# Main.net
KiCad netlist of a schematic drawn in Altium Designer
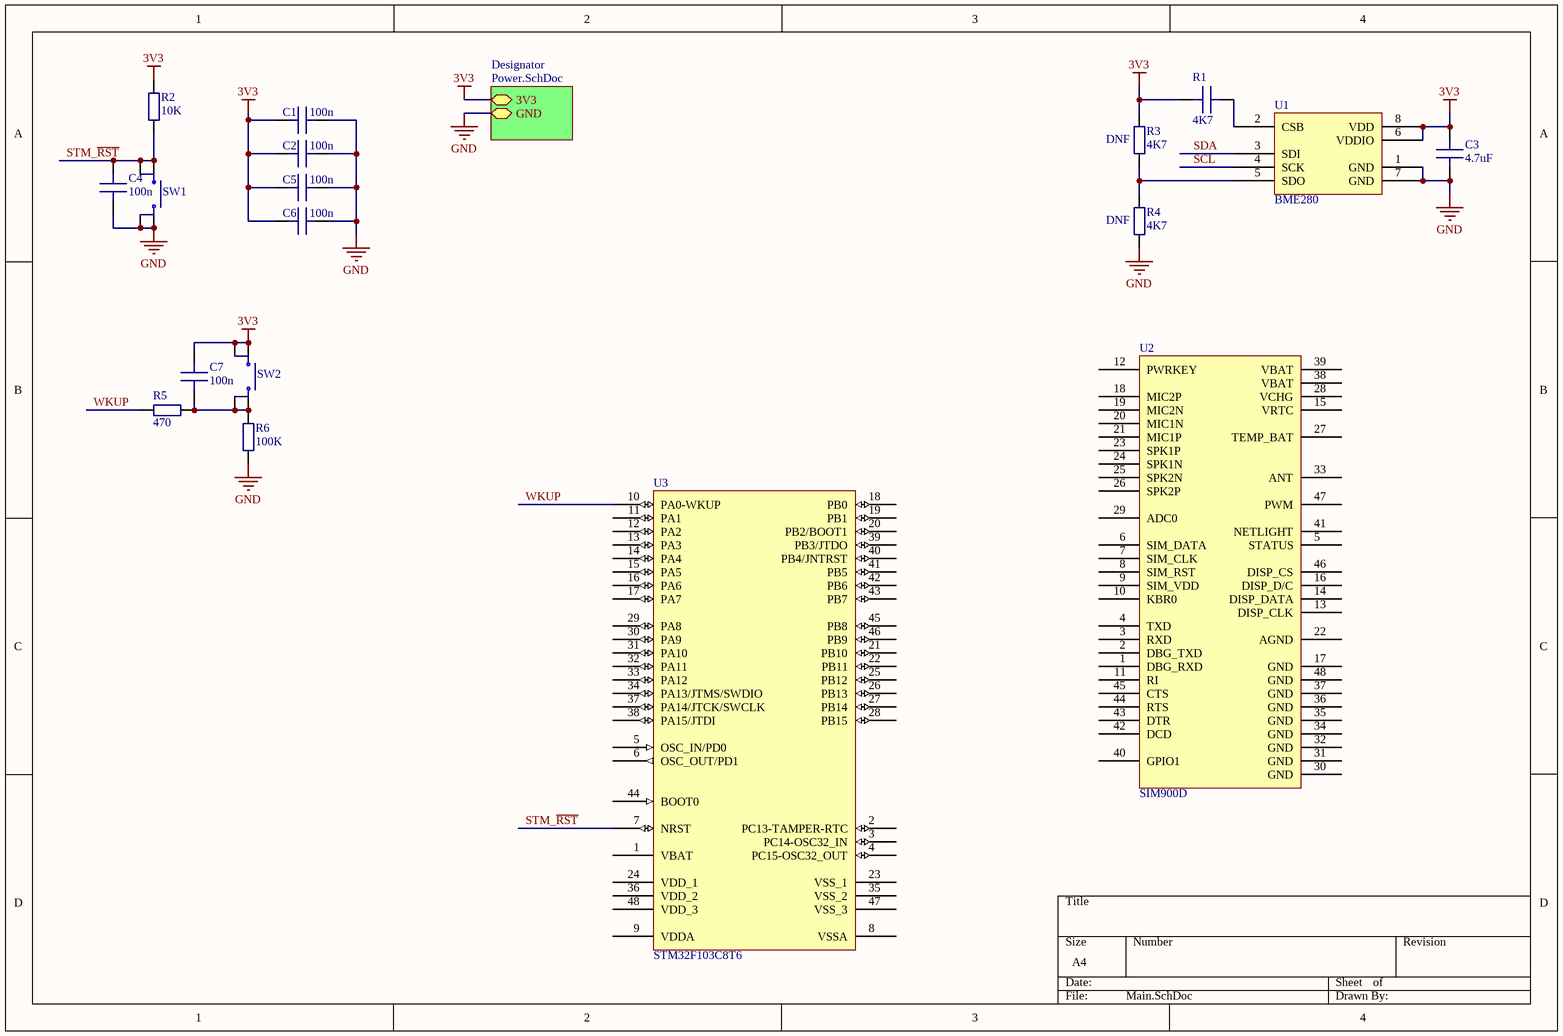
[diagram p0: Main.SchDoc]

(export (version "E")
  (design (tool "Eeschema 10.0.6"))
  (components
    (comp (ref "C1")
      (value "100n")
      (footprint "C0604")
      (description "Capacitor 0603 100n")
      (libsource (lib "ComponentsLib") (part "C0603_100n"))
    )
    (comp (ref "C2")
      (value "100n")
      (footprint "C0604")
      (description "Capacitor 0603 100n")
      (libsource (lib "ComponentsLib") (part "C0603_100n"))
    )
    (comp (ref "C3")
      (value "4.7uF")
      (footprint "C0805")
      (description "Capacitor 0805 4.7uF")
      (libsource (lib "ComponentsLib") (part "C0805_4u7"))
    )
    (comp (ref "C4")
      (value "100n")
      (footprint "C0604")
      (description "Capacitor 0603 100n")
      (libsource (lib "ComponentsLib") (part "C0603_100n"))
    )
    (comp (ref "C5")
      (value "100n")
      (footprint "C0604")
      (description "Capacitor 0603 100n")
      (libsource (lib "ComponentsLib") (part "C0603_100n"))
    )
    (comp (ref "C6")
      (value "100n")
      (footprint "C0604")
      (description "Capacitor 0603 100n")
      (libsource (lib "ComponentsLib") (part "C0603_100n"))
    )
    (comp (ref "C7")
      (value "100n")
      (footprint "C0604")
      (description "Capacitor 0603 100n")
      (libsource (lib "ComponentsLib") (part "C0603_100n"))
    )
    (comp (ref "R1")
      (value "4K7")
      (footprint "R0805")
      (description "Resistor 0805 4K7")
      (libsource (lib "ComponentsLib") (part "R0805_4k7"))
    )
    (comp (ref "R2")
      (value "10K")
      (footprint "R0805")
      (description "Resistor 0805 10K")
      (libsource (lib "ComponentsLib") (part "R0805_10K"))
    )
    (comp (ref "R3")
      (value "4K7")
      (footprint "R0805")
      (description "Resistor 0805 4K7")
      (libsource (lib "") (part "R0805_4k7_1"))
    )
    (comp (ref "R4")
      (value "4K7")
      (footprint "R0805")
      (description "Resistor 0805 4K7")
      (libsource (lib "") (part "R0805_4k7_1"))
    )
    (comp (ref "R5")
      (value "470")
      (footprint "R0805")
      (description "Resistor 0805 470")
      (libsource (lib "ComponentsLib") (part "R0805_470"))
    )
    (comp (ref "R6")
      (value "100K")
      (footprint "R0805")
      (description "Resistor 0805 100K")
      (libsource (lib "ComponentsLib") (part "R0805_100K"))
    )
    (comp (ref "SW1")
      (value "SWITCH_DIP")
      (footprint "SW_GENERIC")
      (description "SWITCH DIP 4.3 mm")
      (libsource (lib "ComponentsLib") (part "SWITCH_DIP"))
    )
    (comp (ref "SW2")
      (value "SWITCH_DIP")
      (footprint "SW_GENERIC")
      (description "SWITCH DIP 4.3 mm")
      (libsource (lib "ComponentsLib") (part "SWITCH_DIP"))
    )
    (comp (ref "U1")
      (value "BME280")
      (footprint "BME280")
      (description "Sensor Temperature humidity")
      (libsource (lib "ComponentsLib") (part "BME280"))
    )
    (comp (ref "U2")
      (value "SIM900D")
      (description "Module: GSM; CSD, GPRS; 2G; 1800MHz, 900MHz; 85.6kbps; I")
      (libsource (lib "ComponentsLib") (part "SIM900D"))
    )
    (comp (ref "U3")
      (value "STM32F103C8T6")
      (footprint "LQFP48_N")
      (description "STM32 ARM-based 32-bit MCU with 64 Kbytes Flash, 48-pin LQFP, Industrial Temperature")
      (fields (field (name "PUBLISHER") "Altium Limited"))
      (libsource (lib "ComponentsLib") (part "STM32F103C8T6"))
    )
  )
  (nets
    (net (code "1") (name "/SCL") (class "Default")
      (node (ref "U1") (pin "4") (pinfunction "SCK_4") (pintype "passive"))
    )
    (net (code "2") (name "/SDA") (class "Default")
      (node (ref "U1") (pin "3") (pinfunction "SDI_3") (pintype "passive"))
    )
    (net (code "3") (name "/STM_~{RST}") (class "Default")
      (node (ref "C4") (pin "1") (pinfunction "1_1") (pintype "passive"))
      (node (ref "R2") (pin "1") (pinfunction "1_1") (pintype "passive"))
      (node (ref "SW1") (pin "1") (pinfunction "1_1") (pintype "passive"))
      (node (ref "SW1") (pin "2") (pinfunction "2_2") (pintype "passive"))
      (node (ref "U3") (pin "7") (pinfunction "NRST_7") (pintype "bidirectional"))
    )
    (net (code "4") (name "/WKUP") (class "Default")
      (node (ref "R5") (pin "1") (pinfunction "1_1") (pintype "passive"))
      (node (ref "U3") (pin "10") (pinfunction "PA0-WKUP_10") (pintype "bidirectional"))
    )
    (net (code "5") (name "3V3") (class "Default")
      (node (ref "C1") (pin "1") (pinfunction "1_1") (pintype "passive"))
      (node (ref "C2") (pin "1") (pinfunction "1_1") (pintype "passive"))
      (node (ref "C3") (pin "2") (pinfunction "2_2") (pintype "passive"))
      (node (ref "C5") (pin "1") (pinfunction "1_1") (pintype "passive"))
      (node (ref "C6") (pin "1") (pinfunction "1_1") (pintype "passive"))
      (node (ref "C7") (pin "2") (pinfunction "2_2") (pintype "passive"))
      (node (ref "R1") (pin "1") (pinfunction "1_1") (pintype "passive"))
      (node (ref "R2") (pin "2") (pinfunction "2_2") (pintype "passive"))
      (node (ref "R3") (pin "2") (pinfunction "2_2") (pintype "passive"))
      (node (ref "SW2") (pin "1") (pinfunction "1_1") (pintype "passive"))
      (node (ref "SW2") (pin "2") (pinfunction "2_2") (pintype "passive"))
      (node (ref "U1") (pin "6") (pinfunction "VDDIO_6") (pintype "passive"))
      (node (ref "U1") (pin "8") (pinfunction "VDD_8") (pintype "passive"))
    )
    (net (code "6") (name "GND") (class "Default")
      (node (ref "C1") (pin "2") (pinfunction "2_2") (pintype "passive"))
      (node (ref "C2") (pin "2") (pinfunction "2_2") (pintype "passive"))
      (node (ref "C3") (pin "1") (pinfunction "1_1") (pintype "passive"))
      (node (ref "C4") (pin "2") (pinfunction "2_2") (pintype "passive"))
      (node (ref "C5") (pin "2") (pinfunction "2_2") (pintype "passive"))
      (node (ref "C6") (pin "2") (pinfunction "2_2") (pintype "passive"))
      (node (ref "R4") (pin "1") (pinfunction "1_1") (pintype "passive"))
      (node (ref "R6") (pin "1") (pinfunction "1_1") (pintype "passive"))
      (node (ref "SW1") (pin "3") (pinfunction "3_3") (pintype "passive"))
      (node (ref "SW1") (pin "4") (pinfunction "4_4") (pintype "passive"))
      (node (ref "U1") (pin "1") (pinfunction "GND_1") (pintype "passive"))
      (node (ref "U1") (pin "7") (pinfunction "GND_7") (pintype "passive"))
    )
    (net (code "7") (name "Net-(C7-Pad1)") (class "Default")
      (node (ref "C7") (pin "1") (pinfunction "1_1") (pintype "passive"))
      (node (ref "R5") (pin "2") (pinfunction "2_2") (pintype "passive"))
      (node (ref "R6") (pin "2") (pinfunction "2_2") (pintype "passive"))
      (node (ref "SW2") (pin "3") (pinfunction "3_3") (pintype "passive"))
      (node (ref "SW2") (pin "4") (pinfunction "4_4") (pintype "passive"))
    )
    (net (code "8") (name "Net-(U1-CSB)") (class "Default")
      (node (ref "R1") (pin "2") (pinfunction "2_2") (pintype "passive"))
      (node (ref "U1") (pin "2") (pinfunction "CSB_2") (pintype "passive"))
    )
    (net (code "9") (name "Net-(U1-SDO)") (class "Default")
      (node (ref "R3") (pin "1") (pinfunction "1_1") (pintype "passive"))
      (node (ref "R4") (pin "2") (pinfunction "2_2") (pintype "passive"))
      (node (ref "U1") (pin "5") (pinfunction "SDO_5") (pintype "passive"))
    )
    (net (code "10") (name "unconnected-(U2-ADC0-Pad29)") (class "Default")
      (node (ref "U2") (pin "29") (pinfunction "ADC0_29") (pintype "passive"))
    )
    (net (code "11") (name "unconnected-(U2-AGND-Pad22)") (class "Default")
      (node (ref "U2") (pin "22") (pinfunction "AGND_22") (pintype "passive"))
    )
    (net (code "12") (name "unconnected-(U2-ANT-Pad33)") (class "Default")
      (node (ref "U2") (pin "33") (pinfunction "ANT_33") (pintype "passive"))
    )
    (net (code "13") (name "unconnected-(U2-CTS-Pad45)") (class "Default")
      (node (ref "U2") (pin "45") (pinfunction "CTS_45") (pintype "passive"))
    )
    (net (code "14") (name "unconnected-(U2-DBG_RXD-Pad1)") (class "Default")
      (node (ref "U2") (pin "1") (pinfunction "DBG_RXD_1") (pintype "passive"))
    )
    (net (code "15") (name "unconnected-(U2-DBG_TXD-Pad2)") (class "Default")
      (node (ref "U2") (pin "2") (pinfunction "DBG_TXD_2") (pintype "passive"))
    )
    (net (code "16") (name "unconnected-(U2-DCD-Pad42)") (class "Default")
      (node (ref "U2") (pin "42") (pinfunction "DCD_42") (pintype "passive"))
    )
    (net (code "17") (name "unconnected-(U2-DISP_CLK-Pad13)") (class "Default")
      (node (ref "U2") (pin "13") (pinfunction "DISP_CLK_13") (pintype "passive"))
    )
    (net (code "18") (name "unconnected-(U2-DISP_CS-Pad46)") (class "Default")
      (node (ref "U2") (pin "46") (pinfunction "DISP_CS_46") (pintype "passive"))
    )
    (net (code "19") (name "unconnected-(U2-DISP_DATA-Pad14)") (class "Default")
      (node (ref "U2") (pin "14") (pinfunction "DISP_DATA_14") (pintype "passive"))
    )
    (net (code "20") (name "unconnected-(U2-DISP_D{slash}C-Pad16)") (class "Default")
      (node (ref "U2") (pin "16") (pinfunction "DISP_D/C_16") (pintype "passive"))
    )
    (net (code "21") (name "unconnected-(U2-DTR-Pad43)") (class "Default")
      (node (ref "U2") (pin "43") (pinfunction "DTR_43") (pintype "passive"))
    )
    (net (code "22") (name "unconnected-(U2-GND-Pad17)") (class "Default")
      (node (ref "U2") (pin "17") (pinfunction "GND_17") (pintype "passive"))
    )
    (net (code "23") (name "unconnected-(U2-GND-Pad30)") (class "Default")
      (node (ref "U2") (pin "30") (pinfunction "GND_30") (pintype "passive"))
    )
    (net (code "24") (name "unconnected-(U2-GND-Pad31)") (class "Default")
      (node (ref "U2") (pin "31") (pinfunction "GND_31") (pintype "passive"))
    )
    (net (code "25") (name "unconnected-(U2-GND-Pad32)") (class "Default")
      (node (ref "U2") (pin "32") (pinfunction "GND_32") (pintype "passive"))
    )
    (net (code "26") (name "unconnected-(U2-GND-Pad34)") (class "Default")
      (node (ref "U2") (pin "34") (pinfunction "GND_34") (pintype "passive"))
    )
    (net (code "27") (name "unconnected-(U2-GND-Pad35)") (class "Default")
      (node (ref "U2") (pin "35") (pinfunction "GND_35") (pintype "passive"))
    )
    (net (code "28") (name "unconnected-(U2-GND-Pad36)") (class "Default")
      (node (ref "U2") (pin "36") (pinfunction "GND_36") (pintype "passive"))
    )
    (net (code "29") (name "unconnected-(U2-GND-Pad37)") (class "Default")
      (node (ref "U2") (pin "37") (pinfunction "GND_37") (pintype "passive"))
    )
    (net (code "30") (name "unconnected-(U2-GND-Pad48)") (class "Default")
      (node (ref "U2") (pin "48") (pinfunction "GND_48") (pintype "passive"))
    )
    (net (code "31") (name "unconnected-(U2-GPIO1-Pad40)") (class "Default")
      (node (ref "U2") (pin "40") (pinfunction "GPIO1_40") (pintype "passive"))
    )
    (net (code "32") (name "unconnected-(U2-KBR0-Pad10)") (class "Default")
      (node (ref "U2") (pin "10") (pinfunction "KBR0_10") (pintype "passive"))
    )
    (net (code "33") (name "unconnected-(U2-MIC1N-Pad20)") (class "Default")
      (node (ref "U2") (pin "20") (pinfunction "MIC1N_20") (pintype "passive"))
    )
    (net (code "34") (name "unconnected-(U2-MIC1P-Pad21)") (class "Default")
      (node (ref "U2") (pin "21") (pinfunction "MIC1P_21") (pintype "passive"))
    )
    (net (code "35") (name "unconnected-(U2-MIC2N-Pad19)") (class "Default")
      (node (ref "U2") (pin "19") (pinfunction "MIC2N_19") (pintype "passive"))
    )
    (net (code "36") (name "unconnected-(U2-MIC2P-Pad18)") (class "Default")
      (node (ref "U2") (pin "18") (pinfunction "MIC2P_18") (pintype "passive"))
    )
    (net (code "37") (name "unconnected-(U2-NETLIGHT-Pad41)") (class "Default")
      (node (ref "U2") (pin "41") (pinfunction "NETLIGHT_41") (pintype "passive"))
    )
    (net (code "38") (name "unconnected-(U2-PWM-Pad47)") (class "Default")
      (node (ref "U2") (pin "47") (pinfunction "PWM_47") (pintype "passive"))
    )
    (net (code "39") (name "unconnected-(U2-PWRKEY-Pad12)") (class "Default")
      (node (ref "U2") (pin "12") (pinfunction "PWRKEY_12") (pintype "passive"))
    )
    (net (code "40") (name "unconnected-(U2-RI-Pad11)") (class "Default")
      (node (ref "U2") (pin "11") (pinfunction "RI_11") (pintype "passive"))
    )
    (net (code "41") (name "unconnected-(U2-RTS-Pad44)") (class "Default")
      (node (ref "U2") (pin "44") (pinfunction "RTS_44") (pintype "passive"))
    )
    (net (code "42") (name "unconnected-(U2-RXD-Pad3)") (class "Default")
      (node (ref "U2") (pin "3") (pinfunction "RXD_3") (pintype "passive"))
    )
    (net (code "43") (name "unconnected-(U2-SIM_CLK-Pad7)") (class "Default")
      (node (ref "U2") (pin "7") (pinfunction "SIM_CLK_7") (pintype "passive"))
    )
    (net (code "44") (name "unconnected-(U2-SIM_DATA-Pad6)") (class "Default")
      (node (ref "U2") (pin "6") (pinfunction "SIM_DATA_6") (pintype "passive"))
    )
    (net (code "45") (name "unconnected-(U2-SIM_RST-Pad8)") (class "Default")
      (node (ref "U2") (pin "8") (pinfunction "SIM_RST_8") (pintype "passive"))
    )
    (net (code "46") (name "unconnected-(U2-SIM_VDD-Pad9)") (class "Default")
      (node (ref "U2") (pin "9") (pinfunction "SIM_VDD_9") (pintype "passive"))
    )
    (net (code "47") (name "unconnected-(U2-SPK1N-Pad24)") (class "Default")
      (node (ref "U2") (pin "24") (pinfunction "SPK1N_24") (pintype "passive"))
    )
    (net (code "48") (name "unconnected-(U2-SPK1P-Pad23)") (class "Default")
      (node (ref "U2") (pin "23") (pinfunction "SPK1P_23") (pintype "passive"))
    )
    (net (code "49") (name "unconnected-(U2-SPK2N-Pad25)") (class "Default")
      (node (ref "U2") (pin "25") (pinfunction "SPK2N_25") (pintype "passive"))
    )
    (net (code "50") (name "unconnected-(U2-SPK2P-Pad26)") (class "Default")
      (node (ref "U2") (pin "26") (pinfunction "SPK2P_26") (pintype "passive"))
    )
    (net (code "51") (name "unconnected-(U2-STATUS-Pad5)") (class "Default")
      (node (ref "U2") (pin "5") (pinfunction "STATUS_5") (pintype "passive"))
    )
    (net (code "52") (name "unconnected-(U2-TEMP_BAT-Pad27)") (class "Default")
      (node (ref "U2") (pin "27") (pinfunction "TEMP_BAT_27") (pintype "passive"))
    )
    (net (code "53") (name "unconnected-(U2-TXD-Pad4)") (class "Default")
      (node (ref "U2") (pin "4") (pinfunction "TXD_4") (pintype "passive"))
    )
    (net (code "54") (name "unconnected-(U2-VBAT-Pad38)") (class "Default")
      (node (ref "U2") (pin "38") (pinfunction "VBAT_38") (pintype "passive"))
    )
    (net (code "55") (name "unconnected-(U2-VBAT-Pad39)") (class "Default")
      (node (ref "U2") (pin "39") (pinfunction "VBAT_39") (pintype "passive"))
    )
    (net (code "56") (name "unconnected-(U2-VCHG-Pad28)") (class "Default")
      (node (ref "U2") (pin "28") (pinfunction "VCHG_28") (pintype "passive"))
    )
    (net (code "57") (name "unconnected-(U2-VRTC-Pad15)") (class "Default")
      (node (ref "U2") (pin "15") (pinfunction "VRTC_15") (pintype "passive"))
    )
    (net (code "58") (name "unconnected-(U3-BOOT0-Pad44)") (class "Default")
      (node (ref "U3") (pin "44") (pinfunction "BOOT0_44") (pintype "input"))
    )
    (net (code "59") (name "unconnected-(U3-OSC_IN{slash}PD0-Pad5)") (class "Default")
      (node (ref "U3") (pin "5") (pinfunction "OSC_IN/PD0_5") (pintype "input"))
    )
    (net (code "60") (name "unconnected-(U3-OSC_OUT{slash}PD1-Pad6)") (class "Default")
      (node (ref "U3") (pin "6") (pinfunction "OSC_OUT/PD1_6") (pintype "output"))
    )
    (net (code "61") (name "unconnected-(U3-PA1-Pad11)") (class "Default")
      (node (ref "U3") (pin "11") (pinfunction "PA1_11") (pintype "bidirectional"))
    )
    (net (code "62") (name "unconnected-(U3-PA2-Pad12)") (class "Default")
      (node (ref "U3") (pin "12") (pinfunction "PA2_12") (pintype "bidirectional"))
    )
    (net (code "63") (name "unconnected-(U3-PA3-Pad13)") (class "Default")
      (node (ref "U3") (pin "13") (pinfunction "PA3_13") (pintype "bidirectional"))
    )
    (net (code "64") (name "unconnected-(U3-PA4-Pad14)") (class "Default")
      (node (ref "U3") (pin "14") (pinfunction "PA4_14") (pintype "bidirectional"))
    )
    (net (code "65") (name "unconnected-(U3-PA5-Pad15)") (class "Default")
      (node (ref "U3") (pin "15") (pinfunction "PA5_15") (pintype "bidirectional"))
    )
    (net (code "66") (name "unconnected-(U3-PA6-Pad16)") (class "Default")
      (node (ref "U3") (pin "16") (pinfunction "PA6_16") (pintype "bidirectional"))
    )
    (net (code "67") (name "unconnected-(U3-PA7-Pad17)") (class "Default")
      (node (ref "U3") (pin "17") (pinfunction "PA7_17") (pintype "bidirectional"))
    )
    (net (code "68") (name "unconnected-(U3-PA8-Pad29)") (class "Default")
      (node (ref "U3") (pin "29") (pinfunction "PA8_29") (pintype "bidirectional"))
    )
    (net (code "69") (name "unconnected-(U3-PA9-Pad30)") (class "Default")
      (node (ref "U3") (pin "30") (pinfunction "PA9_30") (pintype "bidirectional"))
    )
    (net (code "70") (name "unconnected-(U3-PA10-Pad31)") (class "Default")
      (node (ref "U3") (pin "31") (pinfunction "PA10_31") (pintype "bidirectional"))
    )
    (net (code "71") (name "unconnected-(U3-PA11-Pad32)") (class "Default")
      (node (ref "U3") (pin "32") (pinfunction "PA11_32") (pintype "bidirectional"))
    )
    (net (code "72") (name "unconnected-(U3-PA12-Pad33)") (class "Default")
      (node (ref "U3") (pin "33") (pinfunction "PA12_33") (pintype "bidirectional"))
    )
    (net (code "73") (name "unconnected-(U3-PA13{slash}JTMS{slash}SWDIO-Pad34)") (class "Default")
      (node (ref "U3") (pin "34") (pinfunction "PA13/JTMS/SWDIO_34") (pintype "bidirectional"))
    )
    (net (code "74") (name "unconnected-(U3-PA14{slash}JTCK{slash}SWCLK-Pad37)") (class "Default")
      (node (ref "U3") (pin "37") (pinfunction "PA14/JTCK/SWCLK_37") (pintype "bidirectional"))
    )
    (net (code "75") (name "unconnected-(U3-PA15{slash}JTDI-Pad38)") (class "Default")
      (node (ref "U3") (pin "38") (pinfunction "PA15/JTDI_38") (pintype "bidirectional"))
    )
    (net (code "76") (name "unconnected-(U3-PB0-Pad18)") (class "Default")
      (node (ref "U3") (pin "18") (pinfunction "PB0_18") (pintype "bidirectional"))
    )
    (net (code "77") (name "unconnected-(U3-PB1-Pad19)") (class "Default")
      (node (ref "U3") (pin "19") (pinfunction "PB1_19") (pintype "bidirectional"))
    )
    (net (code "78") (name "unconnected-(U3-PB2{slash}BOOT1-Pad20)") (class "Default")
      (node (ref "U3") (pin "20") (pinfunction "PB2/BOOT1_20") (pintype "bidirectional"))
    )
    (net (code "79") (name "unconnected-(U3-PB3{slash}JTDO-Pad39)") (class "Default")
      (node (ref "U3") (pin "39") (pinfunction "PB3/JTDO_39") (pintype "bidirectional"))
    )
    (net (code "80") (name "unconnected-(U3-PB4{slash}JNTRST-Pad40)") (class "Default")
      (node (ref "U3") (pin "40") (pinfunction "PB4/JNTRST_40") (pintype "bidirectional"))
    )
    (net (code "81") (name "unconnected-(U3-PB5-Pad41)") (class "Default")
      (node (ref "U3") (pin "41") (pinfunction "PB5_41") (pintype "bidirectional"))
    )
    (net (code "82") (name "unconnected-(U3-PB6-Pad42)") (class "Default")
      (node (ref "U3") (pin "42") (pinfunction "PB6_42") (pintype "bidirectional"))
    )
    (net (code "83") (name "unconnected-(U3-PB7-Pad43)") (class "Default")
      (node (ref "U3") (pin "43") (pinfunction "PB7_43") (pintype "bidirectional"))
    )
    (net (code "84") (name "unconnected-(U3-PB8-Pad45)") (class "Default")
      (node (ref "U3") (pin "45") (pinfunction "PB8_45") (pintype "bidirectional"))
    )
    (net (code "85") (name "unconnected-(U3-PB9-Pad46)") (class "Default")
      (node (ref "U3") (pin "46") (pinfunction "PB9_46") (pintype "bidirectional"))
    )
    (net (code "86") (name "unconnected-(U3-PB10-Pad21)") (class "Default")
      (node (ref "U3") (pin "21") (pinfunction "PB10_21") (pintype "bidirectional"))
    )
    (net (code "87") (name "unconnected-(U3-PB11-Pad22)") (class "Default")
      (node (ref "U3") (pin "22") (pinfunction "PB11_22") (pintype "bidirectional"))
    )
    (net (code "88") (name "unconnected-(U3-PB12-Pad25)") (class "Default")
      (node (ref "U3") (pin "25") (pinfunction "PB12_25") (pintype "bidirectional"))
    )
    (net (code "89") (name "unconnected-(U3-PB13-Pad26)") (class "Default")
      (node (ref "U3") (pin "26") (pinfunction "PB13_26") (pintype "bidirectional"))
    )
    (net (code "90") (name "unconnected-(U3-PB14-Pad27)") (class "Default")
      (node (ref "U3") (pin "27") (pinfunction "PB14_27") (pintype "bidirectional"))
    )
    (net (code "91") (name "unconnected-(U3-PB15-Pad28)") (class "Default")
      (node (ref "U3") (pin "28") (pinfunction "PB15_28") (pintype "bidirectional"))
    )
    (net (code "92") (name "unconnected-(U3-PC13-TAMPER-RTC-Pad2)") (class "Default")
      (node (ref "U3") (pin "2") (pinfunction "PC13-TAMPER-RTC_2") (pintype "bidirectional"))
    )
    (net (code "93") (name "unconnected-(U3-PC14-OSC32_IN-Pad3)") (class "Default")
      (node (ref "U3") (pin "3") (pinfunction "PC14-OSC32_IN_3") (pintype "bidirectional"))
    )
    (net (code "94") (name "unconnected-(U3-PC15-OSC32_OUT-Pad4)") (class "Default")
      (node (ref "U3") (pin "4") (pinfunction "PC15-OSC32_OUT_4") (pintype "bidirectional"))
    )
    (net (code "95") (name "unconnected-(U3-VBAT-Pad1)") (class "Default")
      (node (ref "U3") (pin "1") (pinfunction "VBAT_1") (pintype "power_in"))
    )
    (net (code "96") (name "unconnected-(U3-VDDA-Pad9)") (class "Default")
      (node (ref "U3") (pin "9") (pinfunction "VDDA_9") (pintype "power_in"))
    )
    (net (code "97") (name "unconnected-(U3-VDD_1-Pad24)") (class "Default")
      (node (ref "U3") (pin "24") (pinfunction "VDD_1_24") (pintype "power_in"))
    )
    (net (code "98") (name "unconnected-(U3-VDD_2-Pad36)") (class "Default")
      (node (ref "U3") (pin "36") (pinfunction "VDD_2_36") (pintype "power_in"))
    )
    (net (code "99") (name "unconnected-(U3-VDD_3-Pad48)") (class "Default")
      (node (ref "U3") (pin "48") (pinfunction "VDD_3_48") (pintype "power_in"))
    )
    (net (code "100") (name "unconnected-(U3-VSSA-Pad8)") (class "Default")
      (node (ref "U3") (pin "8") (pinfunction "VSSA_8") (pintype "power_in"))
    )
    (net (code "101") (name "unconnected-(U3-VSS_1-Pad23)") (class "Default")
      (node (ref "U3") (pin "23") (pinfunction "VSS_1_23") (pintype "power_in"))
    )
    (net (code "102") (name "unconnected-(U3-VSS_2-Pad35)") (class "Default")
      (node (ref "U3") (pin "35") (pinfunction "VSS_2_35") (pintype "power_in"))
    )
    (net (code "103") (name "unconnected-(U3-VSS_3-Pad47)") (class "Default")
      (node (ref "U3") (pin "47") (pinfunction "VSS_3_47") (pintype "power_in"))
    )
  )
)
